# bldcmd_ver1.net
KiCad netlist of a schematic drawn in EAGLE
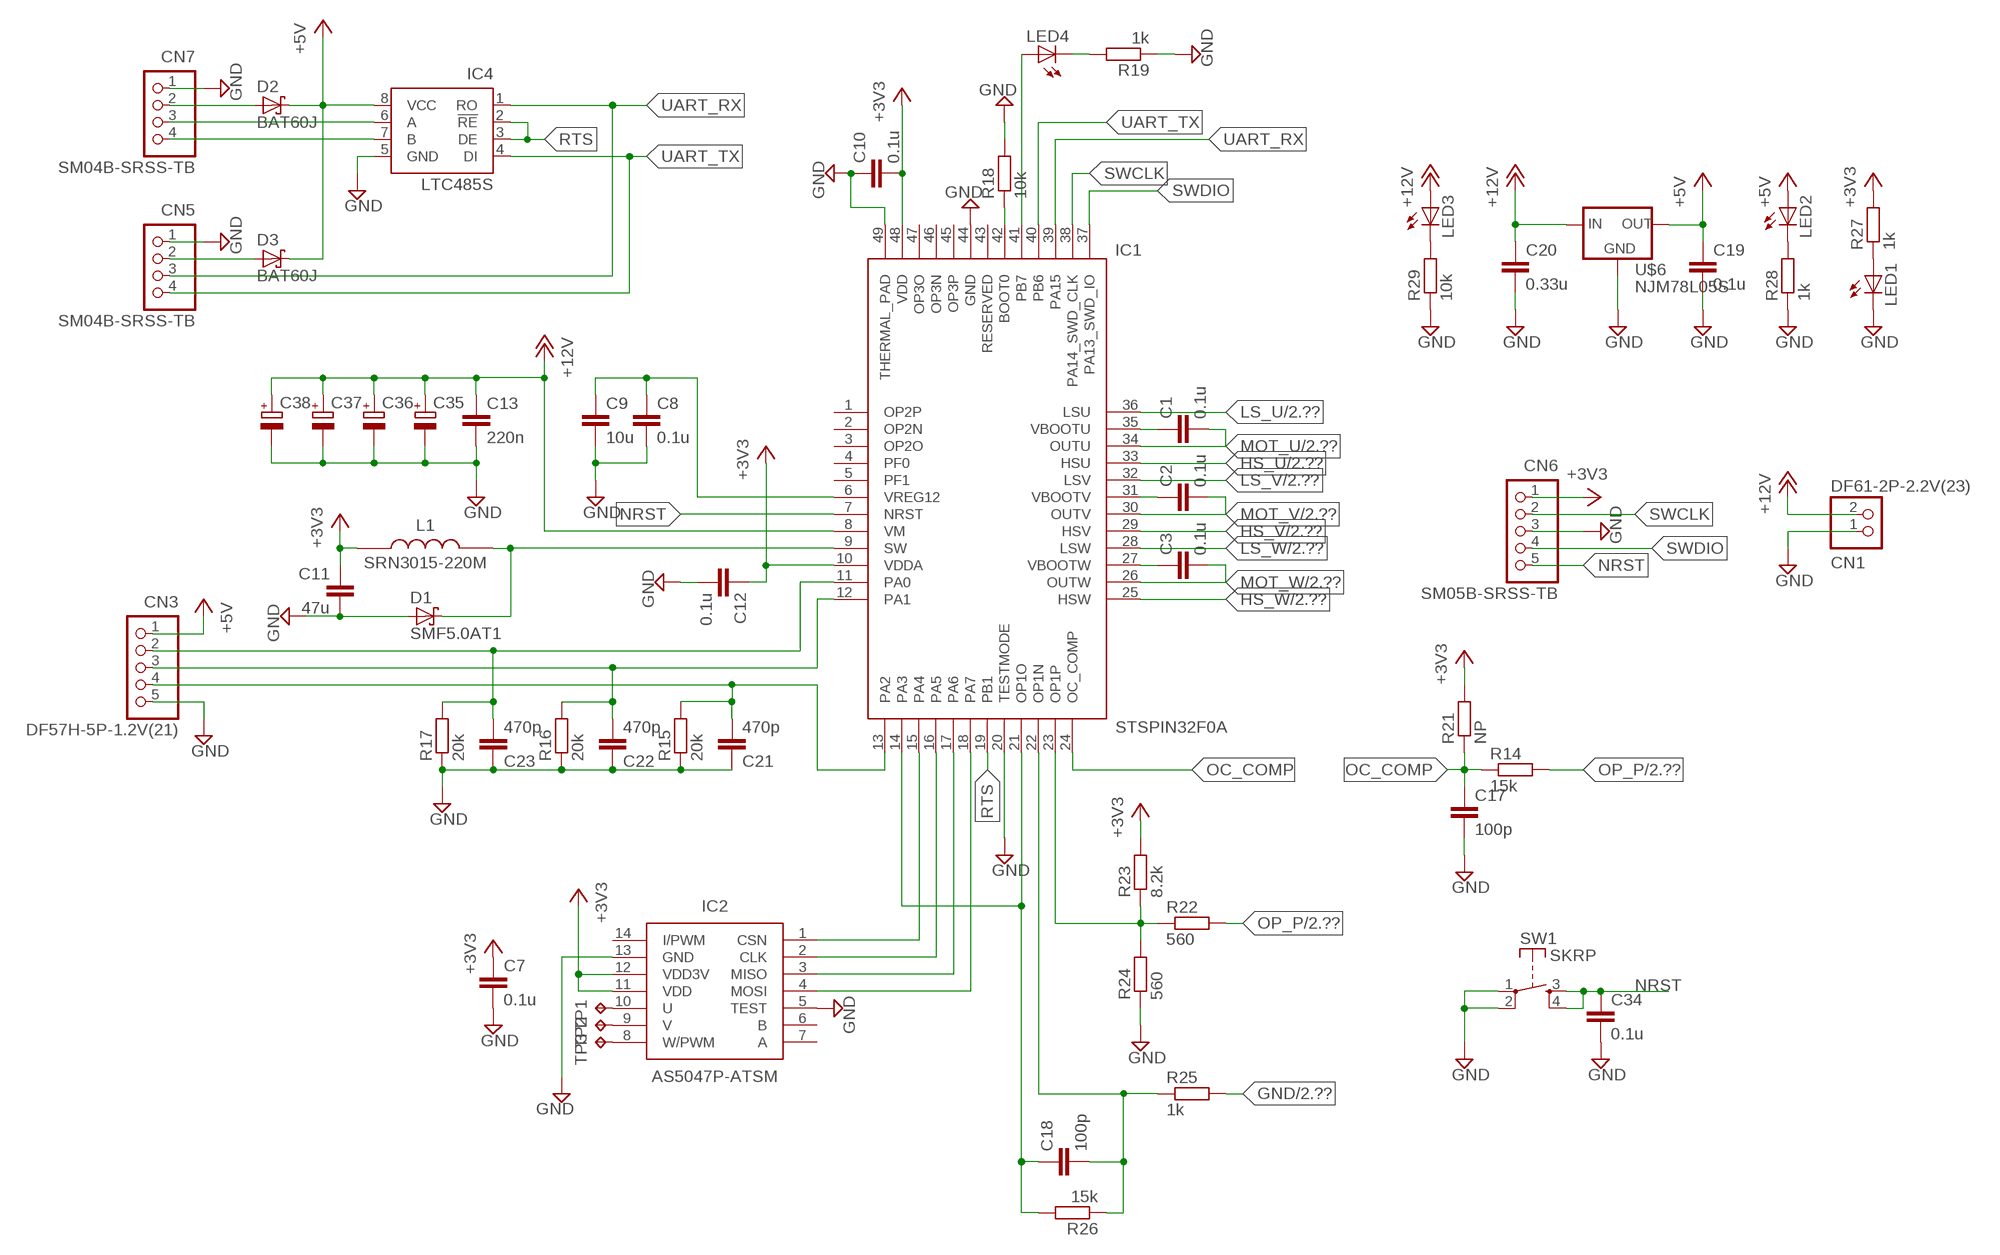
[diagram p0: schematic, sheet 1]
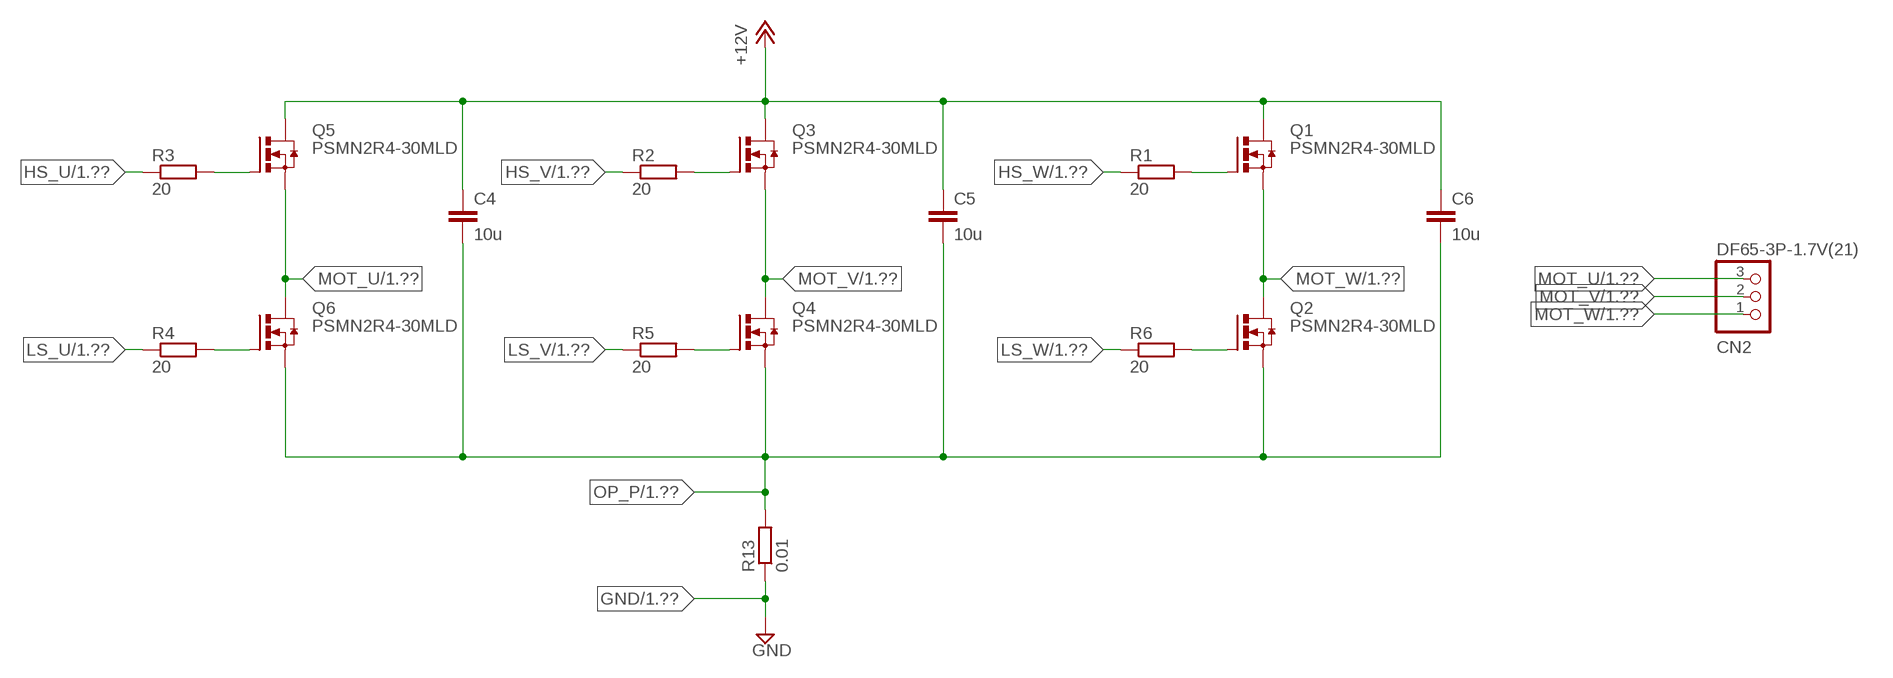
[diagram p1: schematic, sheet 2]

(export (version "E")
  (design (tool "Eeschema 10.0.6"))
  (components
    (comp (ref "C4")
      (value "10u")
      (footprint "eagle-import:C1206")
      (libsource (lib "eagle-import") (part "C-EUC1206"))
    )
    (comp (ref "C5")
      (value "10u")
      (footprint "eagle-import:C1206")
      (libsource (lib "eagle-import") (part "C-EUC1206"))
    )
    (comp (ref "C6")
      (value "10u")
      (footprint "eagle-import:C1206")
      (libsource (lib "eagle-import") (part "C-EUC1206"))
    )
    (comp (ref "CN2")
      (value "DF65-3P-1.7V(21)")
      (footprint "eagle-import:DF65-3P-1.7V")
      (fields (field (name "RS_PART_NUMBER") "8735164"))
      (libsource (lib "eagle-import") (part "DF65-3P-1.7V(21)"))
    )
    (comp (ref "Q1")
      (value "PSMN2R4-30MLD")
      (footprint "eagle-import:LFPAK33")
      (fields (field (name "MF") "Nexperia USA Inc.") (field (name "MPN") "PSMN2R4-30MLD "))
      (libsource (lib "eagle-import") (part "PSMN2R4-30MLD"))
    )
    (comp (ref "Q2")
      (value "PSMN2R4-30MLD")
      (footprint "eagle-import:LFPAK33")
      (fields (field (name "MF") "Nexperia USA Inc.") (field (name "MPN") "PSMN2R4-30MLD "))
      (libsource (lib "eagle-import") (part "PSMN2R4-30MLD"))
    )
    (comp (ref "Q3")
      (value "PSMN2R4-30MLD")
      (footprint "eagle-import:LFPAK33")
      (fields (field (name "MF") "Nexperia USA Inc.") (field (name "MPN") "PSMN2R4-30MLD "))
      (libsource (lib "eagle-import") (part "PSMN2R4-30MLD"))
    )
    (comp (ref "Q4")
      (value "PSMN2R4-30MLD")
      (footprint "eagle-import:LFPAK33")
      (fields (field (name "MF") "Nexperia USA Inc.") (field (name "MPN") "PSMN2R4-30MLD "))
      (libsource (lib "eagle-import") (part "PSMN2R4-30MLD"))
    )
    (comp (ref "Q5")
      (value "PSMN2R4-30MLD")
      (footprint "eagle-import:LFPAK33")
      (fields (field (name "MF") "Nexperia USA Inc.") (field (name "MPN") "PSMN2R4-30MLD "))
      (libsource (lib "eagle-import") (part "PSMN2R4-30MLD"))
    )
    (comp (ref "Q6")
      (value "PSMN2R4-30MLD")
      (footprint "eagle-import:LFPAK33")
      (fields (field (name "MF") "Nexperia USA Inc.") (field (name "MPN") "PSMN2R4-30MLD "))
      (libsource (lib "eagle-import") (part "PSMN2R4-30MLD"))
    )
    (comp (ref "R1")
      (value "20")
      (footprint "eagle-import:R0603")
      (libsource (lib "eagle-import") (part "R-EU_R0603"))
    )
    (comp (ref "R2")
      (value "20")
      (footprint "eagle-import:R0603")
      (libsource (lib "eagle-import") (part "R-EU_R0603"))
    )
    (comp (ref "R3")
      (value "20")
      (footprint "eagle-import:R0603")
      (libsource (lib "eagle-import") (part "R-EU_R0603"))
    )
    (comp (ref "R4")
      (value "20")
      (footprint "eagle-import:R0603")
      (libsource (lib "eagle-import") (part "R-EU_R0603"))
    )
    (comp (ref "R5")
      (value "20")
      (footprint "eagle-import:R0603")
      (libsource (lib "eagle-import") (part "R-EU_R0603"))
    )
    (comp (ref "R6")
      (value "20")
      (footprint "eagle-import:R0603")
      (libsource (lib "eagle-import") (part "R-EU_R0603"))
    )
    (comp (ref "R13")
      (value "0.01")
      (footprint "eagle-import:R3216")
      (libsource (lib "eagle-import") (part "R-EU_R3216"))
    )
    (comp (ref "C1")
      (value "0.1u")
      (footprint "eagle-import:C0402")
      (libsource (lib "eagle-import") (part "C-EUC0402"))
    )
    (comp (ref "C2")
      (value "0.1u")
      (footprint "eagle-import:C0402")
      (libsource (lib "eagle-import") (part "C-EUC0402"))
    )
    (comp (ref "C3")
      (value "0.1u")
      (footprint "eagle-import:C0402")
      (libsource (lib "eagle-import") (part "C-EUC0402"))
    )
    (comp (ref "C7")
      (value "0.1u")
      (footprint "eagle-import:C0603K")
      (libsource (lib "eagle-import") (part "C-EUC0603K"))
    )
    (comp (ref "C8")
      (value "0.1u")
      (footprint "eagle-import:C0603K")
      (libsource (lib "eagle-import") (part "C-EUC0603K"))
    )
    (comp (ref "C9")
      (value "10u")
      (footprint "eagle-import:C0805K")
      (libsource (lib "eagle-import") (part "C-EUC0805K"))
    )
    (comp (ref "C10")
      (value "0.1u")
      (footprint "eagle-import:C0603K")
      (libsource (lib "eagle-import") (part "C-EUC0603K"))
    )
    (comp (ref "C11")
      (value "47u")
      (footprint "eagle-import:C1206K")
      (libsource (lib "eagle-import") (part "C-EUC1206K"))
    )
    (comp (ref "C12")
      (value "0.1u")
      (footprint "eagle-import:C0603K")
      (libsource (lib "eagle-import") (part "C-EUC0603K"))
    )
    (comp (ref "C13")
      (value "220n")
      (footprint "eagle-import:C0805K")
      (libsource (lib "eagle-import") (part "C-EUC0805K"))
    )
    (comp (ref "C17")
      (value "100p")
      (footprint "eagle-import:C0402")
      (libsource (lib "eagle-import") (part "C-EUC0402"))
    )
    (comp (ref "C18")
      (value "100p")
      (footprint "eagle-import:C0402")
      (libsource (lib "eagle-import") (part "C-EUC0402"))
    )
    (comp (ref "C19")
      (value "0.1u")
      (footprint "eagle-import:C0603K")
      (libsource (lib "eagle-import") (part "C-EUC0603K"))
    )
    (comp (ref "C20")
      (value "0.33u")
      (footprint "eagle-import:C0805K")
      (libsource (lib "eagle-import") (part "C-EUC0805K"))
    )
    (comp (ref "C21")
      (value "470p")
      (footprint "eagle-import:C0402")
      (libsource (lib "eagle-import") (part "C-EUC0402"))
    )
    (comp (ref "C22")
      (value "470p")
      (footprint "eagle-import:C0402")
      (libsource (lib "eagle-import") (part "C-EUC0402"))
    )
    (comp (ref "C23")
      (value "470p")
      (footprint "eagle-import:C0402")
      (libsource (lib "eagle-import") (part "C-EUC0402"))
    )
    (comp (ref "C34")
      (value "0.1u")
      (footprint "eagle-import:C0603K")
      (libsource (lib "eagle-import") (part "C-EUC0603K"))
    )
    (comp (ref "C35")
      (value "CPOL-EU153CLV-0605")
      (footprint "eagle-import:153CLV-0605")
      (libsource (lib "eagle-import") (part "CPOL-EU153CLV-0605"))
    )
    (comp (ref "C36")
      (value "CPOL-EU153CLV-0605")
      (footprint "eagle-import:153CLV-0605")
      (libsource (lib "eagle-import") (part "CPOL-EU153CLV-0605"))
    )
    (comp (ref "C37")
      (value "CPOL-EU153CLV-0605")
      (footprint "eagle-import:153CLV-0605")
      (libsource (lib "eagle-import") (part "CPOL-EU153CLV-0605"))
    )
    (comp (ref "C38")
      (value "CPOL-EU153CLV-0605")
      (footprint "eagle-import:153CLV-0605")
      (libsource (lib "eagle-import") (part "CPOL-EU153CLV-0605"))
    )
    (comp (ref "CN1")
      (value "DF61-2P-2.2V(23)")
      (footprint "eagle-import:DF61-2P-2.2V")
      (fields (field (name "RS_PART_NUMBER") "7922837P"))
      (libsource (lib "eagle-import") (part "DF61-2P-2.2V(23)"))
    )
    (comp (ref "CN3")
      (value "DF57H-5P-1.2V(21)")
      (footprint "eagle-import:DF57H-5P-1.2V(21)")
      (libsource (lib "eagle-import") (part "DF57H-5P-1.2V(21)"))
    )
    (comp (ref "CN5")
      (value "SM04B-SRSS-TB")
      (footprint "eagle-import:SM04B-SRSS-TB")
      (libsource (lib "eagle-import") (part "?M04B-SRSS-TBS"))
    )
    (comp (ref "CN6")
      (value "SM05B-SRSS-TB")
      (footprint "eagle-import:SM05B-SRSS-TB")
      (libsource (lib "eagle-import") (part "?M05B-SRSS-TBS"))
    )
    (comp (ref "CN7")
      (value "SM04B-SRSS-TB")
      (footprint "eagle-import:SM04B-SRSS-TB")
      (libsource (lib "eagle-import") (part "?M04B-SRSS-TBS"))
    )
    (comp (ref "D1")
      (value "SMF5.0AT1")
      (footprint "eagle-import:SOD123FL")
      (libsource (lib "eagle-import") (part "SMF5.0AT1"))
    )
    (comp (ref "D2")
      (value "BAT60J")
      (footprint "eagle-import:SOD323_ST")
      (libsource (lib "eagle-import") (part "BAT60J"))
    )
    (comp (ref "D3")
      (value "BAT60J")
      (footprint "eagle-import:SOD323_ST")
      (libsource (lib "eagle-import") (part "BAT60J"))
    )
    (comp (ref "IC1")
      (value "STSPIN32F0A")
      (footprint "eagle-import:VFQFPN48_7X7X1.0-48L")
      (fields (field (name "MANUFACTURER_PART_NUMBER") "STSPIN32F0ATR"))
      (libsource (lib "eagle-import") (part "STSPIN32F0A"))
    )
    (comp (ref "IC2")
      (value "AS5047P-ATSM")
      (footprint "eagle-import:SOP65P640X120-14N")
      (libsource (lib "eagle-import") (part "AS5047P-ATSM"))
    )
    (comp (ref "IC4")
      (value "LTC485S")
      (footprint "eagle-import:SOIC8")
      (libsource (lib "eagle-import") (part "LTC485S"))
    )
    (comp (ref "L1")
      (value "SRN3015-220M")
      (footprint "eagle-import:SRN3015")
      (fields (field (name "RS_PART_NUMBER") "7435087"))
      (libsource (lib "eagle-import") (part "SRN3015-220M"))
    )
    (comp (ref "LED1")
      (value "LEDSML0603")
      (footprint "eagle-import:SML0603")
      (libsource (lib "eagle-import") (part "LEDSML0603"))
    )
    (comp (ref "LED2")
      (value "LEDSML0603")
      (footprint "eagle-import:SML0603")
      (libsource (lib "eagle-import") (part "LEDSML0603"))
    )
    (comp (ref "LED3")
      (value "LEDSML0603")
      (footprint "eagle-import:SML0603")
      (libsource (lib "eagle-import") (part "LEDSML0603"))
    )
    (comp (ref "LED4")
      (value "LEDSML0603")
      (footprint "eagle-import:SML0603")
      (libsource (lib "eagle-import") (part "LEDSML0603"))
    )
    (comp (ref "R14")
      (value "15k")
      (footprint "eagle-import:R0402")
      (libsource (lib "eagle-import") (part "R-EU_R0402"))
    )
    (comp (ref "R15")
      (value "20k")
      (footprint "eagle-import:R0402")
      (libsource (lib "eagle-import") (part "R-EU_R0402"))
    )
    (comp (ref "R16")
      (value "20k")
      (footprint "eagle-import:R0402")
      (libsource (lib "eagle-import") (part "R-EU_R0402"))
    )
    (comp (ref "R17")
      (value "20k")
      (footprint "eagle-import:R0402")
      (libsource (lib "eagle-import") (part "R-EU_R0402"))
    )
    (comp (ref "R18")
      (value "10k")
      (footprint "eagle-import:R0402")
      (libsource (lib "eagle-import") (part "R-EU_R0402"))
    )
    (comp (ref "R19")
      (value "1k")
      (footprint "eagle-import:R0603")
      (libsource (lib "eagle-import") (part "R-EU_R0603"))
    )
    (comp (ref "R21")
      (value "NP")
      (footprint "eagle-import:R0402")
      (libsource (lib "eagle-import") (part "R-EU_R0402"))
    )
    (comp (ref "R22")
      (value "560")
      (footprint "eagle-import:R0402")
      (libsource (lib "eagle-import") (part "R-EU_R0402"))
    )
    (comp (ref "R23")
      (value "8.2k")
      (footprint "eagle-import:R0402")
      (libsource (lib "eagle-import") (part "R-EU_R0402"))
    )
    (comp (ref "R24")
      (value "560")
      (footprint "eagle-import:R0402")
      (libsource (lib "eagle-import") (part "R-EU_R0402"))
    )
    (comp (ref "R25")
      (value "1k")
      (footprint "eagle-import:R0402")
      (libsource (lib "eagle-import") (part "R-EU_R0402"))
    )
    (comp (ref "R26")
      (value "15k")
      (footprint "eagle-import:R0402")
      (libsource (lib "eagle-import") (part "R-EU_R0402"))
    )
    (comp (ref "R27")
      (value "1k")
      (footprint "eagle-import:R0603")
      (libsource (lib "eagle-import") (part "R-EU_R0603"))
    )
    (comp (ref "R28")
      (value "1k")
      (footprint "eagle-import:R0603")
      (libsource (lib "eagle-import") (part "R-EU_R0603"))
    )
    (comp (ref "R29")
      (value "10k")
      (footprint "eagle-import:R0603")
      (libsource (lib "eagle-import") (part "R-EU_R0603"))
    )
    (comp (ref "SW1")
      (value "SKRP")
      (footprint "eagle-import:SKRP")
      (libsource (lib "eagle-import") (part "SKRP"))
    )
    (comp (ref "TP1")
      (value "TPTP08R")
      (footprint "eagle-import:TP08R")
      (libsource (lib "eagle-import") (part "TPTP08R"))
    )
    (comp (ref "TP2")
      (value "TPTP08R")
      (footprint "eagle-import:TP08R")
      (libsource (lib "eagle-import") (part "TPTP08R"))
    )
    (comp (ref "TP3")
      (value "TPTP08R")
      (footprint "eagle-import:TP08R")
      (libsource (lib "eagle-import") (part "TPTP08R"))
    )
    (comp (ref "U$6")
      (value "NJM78L05S")
      (footprint "eagle-import:SOT89R")
      (libsource (lib "eagle-import") (part "NJM78L?S05"))
    )
  )
  (nets
    (net (code "1") (name "+3V3") (class "Default")
      (node (ref "C10") (pin "2") (pinfunction "2_2") (pintype "passive"))
      (node (ref "C11") (pin "1") (pinfunction "1_1") (pintype "passive"))
      (node (ref "C12") (pin "1") (pinfunction "1_1") (pintype "passive"))
      (node (ref "C7") (pin "1") (pinfunction "1_1") (pintype "passive"))
      (node (ref "CN6") (pin "1") (pinfunction "1_1") (pintype "passive"))
      (node (ref "IC1") (pin "10") (pinfunction "VDDA_10") (pintype "passive"))
      (node (ref "IC1") (pin "48") (pinfunction "VDD_48") (pintype "passive"))
      (node (ref "IC2") (pin "11") (pinfunction "VDD_11") (pintype "passive"))
      (node (ref "IC2") (pin "12") (pinfunction "VDD3V_12") (pintype "passive"))
      (node (ref "L1") (pin "1") (pinfunction "1_1") (pintype "bidirectional"))
      (node (ref "R21") (pin "2") (pinfunction "2_2") (pintype "passive"))
      (node (ref "R23") (pin "2") (pinfunction "2_2") (pintype "passive"))
      (node (ref "R27") (pin "2") (pinfunction "2_2") (pintype "passive"))
    )
    (net (code "2") (name "+5V") (class "Default")
      (node (ref "C19") (pin "1") (pinfunction "1_1") (pintype "passive"))
      (node (ref "CN3") (pin "1") (pinfunction "1_1") (pintype "passive"))
      (node (ref "D2") (pin "C") (pinfunction "C_C") (pintype "passive"))
      (node (ref "D3") (pin "C") (pinfunction "C_C") (pintype "passive"))
      (node (ref "IC4") (pin "8") (pinfunction "VCC_8") (pintype "input"))
      (node (ref "LED2") (pin "A") (pinfunction "A_A") (pintype "passive"))
      (node (ref "U$6") (pin "2") (pinfunction "OUT_2") (pintype "passive"))
    )
    (net (code "3") (name "+12V") (class "Default")
      (node (ref "C13") (pin "1") (pinfunction "1_1") (pintype "passive"))
      (node (ref "C20") (pin "1") (pinfunction "1_1") (pintype "passive"))
      (node (ref "C35") (pin "+") (pinfunction "+_+") (pintype "passive"))
      (node (ref "C36") (pin "+") (pinfunction "+_+") (pintype "passive"))
      (node (ref "C37") (pin "+") (pinfunction "+_+") (pintype "passive"))
      (node (ref "C38") (pin "+") (pinfunction "+_+") (pintype "passive"))
      (node (ref "C4") (pin "1") (pinfunction "1_1") (pintype "passive"))
      (node (ref "C5") (pin "1") (pinfunction "1_1") (pintype "passive"))
      (node (ref "C6") (pin "1") (pinfunction "1_1") (pintype "passive"))
      (node (ref "CN1") (pin "2") (pinfunction "2_2") (pintype "passive"))
      (node (ref "IC1") (pin "8") (pinfunction "VM_8") (pintype "passive"))
      (node (ref "LED3") (pin "A") (pinfunction "A_A") (pintype "passive"))
      (node (ref "Q1") (pin "MB") (pinfunction "D_MB") (pintype "passive"))
      (node (ref "Q3") (pin "MB") (pinfunction "D_MB") (pintype "passive"))
      (node (ref "Q5") (pin "MB") (pinfunction "D_MB") (pintype "passive"))
      (node (ref "U$6") (pin "1") (pinfunction "IN_1") (pintype "input"))
    )
    (net (code "4") (name "GND") (class "Default")
      (node (ref "C10") (pin "1") (pinfunction "1_1") (pintype "passive"))
      (node (ref "C11") (pin "2") (pinfunction "2_2") (pintype "passive"))
      (node (ref "C12") (pin "2") (pinfunction "2_2") (pintype "passive"))
      (node (ref "C13") (pin "2") (pinfunction "2_2") (pintype "passive"))
      (node (ref "C17") (pin "2") (pinfunction "2_2") (pintype "passive"))
      (node (ref "C19") (pin "2") (pinfunction "2_2") (pintype "passive"))
      (node (ref "C20") (pin "2") (pinfunction "2_2") (pintype "passive"))
      (node (ref "C21") (pin "1") (pinfunction "1_1") (pintype "passive"))
      (node (ref "C22") (pin "1") (pinfunction "1_1") (pintype "passive"))
      (node (ref "C23") (pin "1") (pinfunction "1_1") (pintype "passive"))
      (node (ref "C34") (pin "2") (pinfunction "2_2") (pintype "passive"))
      (node (ref "C35") (pin "-") (pinfunction "-_-") (pintype "passive"))
      (node (ref "C36") (pin "-") (pinfunction "-_-") (pintype "passive"))
      (node (ref "C37") (pin "-") (pinfunction "-_-") (pintype "passive"))
      (node (ref "C38") (pin "-") (pinfunction "-_-") (pintype "passive"))
      (node (ref "C7") (pin "2") (pinfunction "2_2") (pintype "passive"))
      (node (ref "C8") (pin "2") (pinfunction "2_2") (pintype "passive"))
      (node (ref "C9") (pin "2") (pinfunction "2_2") (pintype "passive"))
      (node (ref "CN1") (pin "1") (pinfunction "1_1") (pintype "passive"))
      (node (ref "CN3") (pin "5") (pinfunction "5_5") (pintype "passive"))
      (node (ref "CN5") (pin "1") (pinfunction "1_1") (pintype "passive"))
      (node (ref "CN6") (pin "3") (pinfunction "3_3") (pintype "passive"))
      (node (ref "CN7") (pin "1") (pinfunction "1_1") (pintype "passive"))
      (node (ref "D1") (pin "A") (pinfunction "A_A") (pintype "passive"))
      (node (ref "IC1") (pin "20") (pinfunction "TESTMODE_20") (pintype "passive"))
      (node (ref "IC1") (pin "44") (pinfunction "GND_44") (pintype "passive"))
      (node (ref "IC1") (pin "49") (pinfunction "THERMAL_PAD_49") (pintype "passive"))
      (node (ref "IC2") (pin "13") (pinfunction "GND_13") (pintype "passive"))
      (node (ref "IC2") (pin "5") (pinfunction "TEST_5") (pintype "passive"))
      (node (ref "IC4") (pin "5") (pinfunction "GND_5") (pintype "input"))
      (node (ref "LED1") (pin "C") (pinfunction "C_C") (pintype "passive"))
      (node (ref "R13") (pin "1") (pinfunction "1_1") (pintype "passive"))
      (node (ref "R15") (pin "1") (pinfunction "1_1") (pintype "passive"))
      (node (ref "R16") (pin "1") (pinfunction "1_1") (pintype "passive"))
      (node (ref "R17") (pin "1") (pinfunction "1_1") (pintype "passive"))
      (node (ref "R18") (pin "2") (pinfunction "2_2") (pintype "passive"))
      (node (ref "R19") (pin "1") (pinfunction "1_1") (pintype "passive"))
      (node (ref "R24") (pin "1") (pinfunction "1_1") (pintype "passive"))
      (node (ref "R25") (pin "2") (pinfunction "2_2") (pintype "passive"))
      (node (ref "R28") (pin "1") (pinfunction "1_1") (pintype "passive"))
      (node (ref "R29") (pin "1") (pinfunction "1_1") (pintype "passive"))
      (node (ref "SW1") (pin "1") (pinfunction "1_1") (pintype "passive"))
      (node (ref "SW1") (pin "2") (pinfunction "2_2") (pintype "passive"))
      (node (ref "U$6") (pin "3") (pinfunction "GND_3") (pintype "input"))
      (node (ref "U$6") (pin "4") (pinfunction "GND_4") (pintype "input"))
    )
    (net (code "5") (name "HS_U") (class "Default")
      (node (ref "IC1") (pin "33") (pinfunction "HSU_33") (pintype "passive"))
      (node (ref "R3") (pin "1") (pinfunction "1_1") (pintype "passive"))
    )
    (net (code "6") (name "HS_V") (class "Default")
      (node (ref "IC1") (pin "29") (pinfunction "HSV_29") (pintype "passive"))
      (node (ref "R2") (pin "1") (pinfunction "1_1") (pintype "passive"))
    )
    (net (code "7") (name "HS_W") (class "Default")
      (node (ref "IC1") (pin "25") (pinfunction "HSW_25") (pintype "passive"))
      (node (ref "R1") (pin "1") (pinfunction "1_1") (pintype "passive"))
    )
    (net (code "8") (name "LS_U") (class "Default")
      (node (ref "IC1") (pin "36") (pinfunction "LSU_36") (pintype "passive"))
      (node (ref "R4") (pin "1") (pinfunction "1_1") (pintype "passive"))
    )
    (net (code "9") (name "LS_V") (class "Default")
      (node (ref "IC1") (pin "32") (pinfunction "LSV_32") (pintype "passive"))
      (node (ref "R5") (pin "1") (pinfunction "1_1") (pintype "passive"))
    )
    (net (code "10") (name "LS_W") (class "Default")
      (node (ref "IC1") (pin "28") (pinfunction "LSW_28") (pintype "passive"))
      (node (ref "R6") (pin "1") (pinfunction "1_1") (pintype "passive"))
    )
    (net (code "11") (name "MOT_U") (class "Default")
      (node (ref "C1") (pin "2") (pinfunction "2_2") (pintype "passive"))
      (node (ref "CN2") (pin "3") (pinfunction "3_3") (pintype "passive"))
      (node (ref "IC1") (pin "34") (pinfunction "OUTU_34") (pintype "passive"))
      (node (ref "Q5") (pin "1") (pinfunction "S_1") (pintype "passive"))
      (node (ref "Q5") (pin "2") (pinfunction "S_2") (pintype "passive"))
      (node (ref "Q5") (pin "3") (pinfunction "S_3") (pintype "passive"))
      (node (ref "Q6") (pin "MB") (pinfunction "D_MB") (pintype "passive"))
    )
    (net (code "12") (name "MOT_V") (class "Default")
      (node (ref "C2") (pin "2") (pinfunction "2_2") (pintype "passive"))
      (node (ref "CN2") (pin "2") (pinfunction "2_2") (pintype "passive"))
      (node (ref "IC1") (pin "30") (pinfunction "OUTV_30") (pintype "passive"))
      (node (ref "Q3") (pin "1") (pinfunction "S_1") (pintype "passive"))
      (node (ref "Q3") (pin "2") (pinfunction "S_2") (pintype "passive"))
      (node (ref "Q3") (pin "3") (pinfunction "S_3") (pintype "passive"))
      (node (ref "Q4") (pin "MB") (pinfunction "D_MB") (pintype "passive"))
    )
    (net (code "13") (name "MOT_W") (class "Default")
      (node (ref "C3") (pin "2") (pinfunction "2_2") (pintype "passive"))
      (node (ref "CN2") (pin "1") (pinfunction "1_1") (pintype "passive"))
      (node (ref "IC1") (pin "26") (pinfunction "OUTW_26") (pintype "passive"))
      (node (ref "Q1") (pin "1") (pinfunction "S_1") (pintype "passive"))
      (node (ref "Q1") (pin "2") (pinfunction "S_2") (pintype "passive"))
      (node (ref "Q1") (pin "3") (pinfunction "S_3") (pintype "passive"))
      (node (ref "Q2") (pin "MB") (pinfunction "D_MB") (pintype "passive"))
    )
    (net (code "14") (name "NRST") (class "Default")
      (node (ref "C34") (pin "1") (pinfunction "1_1") (pintype "passive"))
      (node (ref "CN6") (pin "5") (pinfunction "5_5") (pintype "passive"))
      (node (ref "IC1") (pin "7") (pinfunction "NRST_7") (pintype "passive"))
      (node (ref "SW1") (pin "3") (pinfunction "3_3") (pintype "passive"))
      (node (ref "SW1") (pin "4") (pinfunction "4_4") (pintype "passive"))
    )
    (net (code "15") (name "Net-(CN5-Pad2)") (class "Default")
      (node (ref "CN5") (pin "2") (pinfunction "2_2") (pintype "passive"))
      (node (ref "D3") (pin "A") (pinfunction "A_A") (pintype "passive"))
    )
    (net (code "16") (name "Net-(CN7-Pad2)") (class "Default")
      (node (ref "CN7") (pin "2") (pinfunction "2_2") (pintype "passive"))
      (node (ref "D2") (pin "A") (pinfunction "A_A") (pintype "passive"))
    )
    (net (code "17") (name "Net-(IC1-BOOT0)") (class "Default")
      (node (ref "IC1") (pin "42") (pinfunction "BOOT0_42") (pintype "passive"))
      (node (ref "R18") (pin "1") (pinfunction "1_1") (pintype "passive"))
    )
    (net (code "18") (name "Net-(IC1-OP1N)") (class "Default")
      (node (ref "C18") (pin "2") (pinfunction "2_2") (pintype "passive"))
      (node (ref "IC1") (pin "22") (pinfunction "OP1N_22") (pintype "passive"))
      (node (ref "R25") (pin "1") (pinfunction "1_1") (pintype "passive"))
      (node (ref "R26") (pin "1") (pinfunction "1_1") (pintype "passive"))
    )
    (net (code "19") (name "Net-(IC1-OP1O)") (class "Default")
      (node (ref "C18") (pin "1") (pinfunction "1_1") (pintype "passive"))
      (node (ref "IC1") (pin "14") (pinfunction "PA3_14") (pintype "passive"))
      (node (ref "IC1") (pin "21") (pinfunction "OP1O_21") (pintype "passive"))
      (node (ref "R26") (pin "2") (pinfunction "2_2") (pintype "passive"))
    )
    (net (code "20") (name "Net-(IC1-OP1P)") (class "Default")
      (node (ref "IC1") (pin "23") (pinfunction "OP1P_23") (pintype "passive"))
      (node (ref "R22") (pin "1") (pinfunction "1_1") (pintype "passive"))
      (node (ref "R23") (pin "1") (pinfunction "1_1") (pintype "passive"))
      (node (ref "R24") (pin "2") (pinfunction "2_2") (pintype "passive"))
    )
    (net (code "21") (name "Net-(IC1-PA0)") (class "Default")
      (node (ref "C23") (pin "2") (pinfunction "2_2") (pintype "passive"))
      (node (ref "CN3") (pin "2") (pinfunction "2_2") (pintype "passive"))
      (node (ref "IC1") (pin "11") (pinfunction "PA0_11") (pintype "passive"))
      (node (ref "R17") (pin "2") (pinfunction "2_2") (pintype "passive"))
    )
    (net (code "22") (name "Net-(IC1-PA1)") (class "Default")
      (node (ref "C22") (pin "2") (pinfunction "2_2") (pintype "passive"))
      (node (ref "CN3") (pin "3") (pinfunction "3_3") (pintype "passive"))
      (node (ref "IC1") (pin "12") (pinfunction "PA1_12") (pintype "passive"))
      (node (ref "R16") (pin "2") (pinfunction "2_2") (pintype "passive"))
    )
    (net (code "23") (name "Net-(IC1-PA2)") (class "Default")
      (node (ref "C21") (pin "2") (pinfunction "2_2") (pintype "passive"))
      (node (ref "CN3") (pin "4") (pinfunction "4_4") (pintype "passive"))
      (node (ref "IC1") (pin "13") (pinfunction "PA2_13") (pintype "passive"))
      (node (ref "R15") (pin "2") (pinfunction "2_2") (pintype "passive"))
    )
    (net (code "24") (name "Net-(IC1-PA4)") (class "Default")
      (node (ref "IC1") (pin "15") (pinfunction "PA4_15") (pintype "passive"))
      (node (ref "IC2") (pin "1") (pinfunction "CSN_1") (pintype "passive"))
    )
    (net (code "25") (name "Net-(IC1-PA5)") (class "Default")
      (node (ref "IC1") (pin "16") (pinfunction "PA5_16") (pintype "passive"))
      (node (ref "IC2") (pin "2") (pinfunction "CLK_2") (pintype "passive"))
    )
    (net (code "26") (name "Net-(IC1-PA6)") (class "Default")
      (node (ref "IC1") (pin "17") (pinfunction "PA6_17") (pintype "passive"))
      (node (ref "IC2") (pin "3") (pinfunction "MISO_3") (pintype "passive"))
    )
    (net (code "27") (name "Net-(IC1-PA7)") (class "Default")
      (node (ref "IC1") (pin "18") (pinfunction "PA7_18") (pintype "passive"))
      (node (ref "IC2") (pin "4") (pinfunction "MOSI_4") (pintype "passive"))
    )
    (net (code "28") (name "Net-(IC1-PB7)") (class "Default")
      (node (ref "IC1") (pin "41") (pinfunction "PB7_41") (pintype "passive"))
      (node (ref "LED4") (pin "A") (pinfunction "A_A") (pintype "passive"))
    )
    (net (code "29") (name "Net-(IC1-SW)") (class "Default")
      (node (ref "D1") (pin "C") (pinfunction "C_C") (pintype "passive"))
      (node (ref "IC1") (pin "9") (pinfunction "SW_9") (pintype "passive"))
      (node (ref "L1") (pin "2") (pinfunction "2_2") (pintype "bidirectional"))
    )
    (net (code "30") (name "Net-(IC1-VBOOTU)") (class "Default")
      (node (ref "C1") (pin "1") (pinfunction "1_1") (pintype "passive"))
      (node (ref "IC1") (pin "35") (pinfunction "VBOOTU_35") (pintype "passive"))
    )
    (net (code "31") (name "Net-(IC1-VBOOTV)") (class "Default")
      (node (ref "C2") (pin "1") (pinfunction "1_1") (pintype "passive"))
      (node (ref "IC1") (pin "31") (pinfunction "VBOOTV_31") (pintype "passive"))
    )
    (net (code "32") (name "Net-(IC1-VBOOTW)") (class "Default")
      (node (ref "C3") (pin "1") (pinfunction "1_1") (pintype "passive"))
      (node (ref "IC1") (pin "27") (pinfunction "VBOOTW_27") (pintype "passive"))
    )
    (net (code "33") (name "Net-(IC1-VREG12)") (class "Default")
      (node (ref "C8") (pin "1") (pinfunction "1_1") (pintype "passive"))
      (node (ref "C9") (pin "1") (pinfunction "1_1") (pintype "passive"))
      (node (ref "IC1") (pin "6") (pinfunction "VREG12_6") (pintype "passive"))
    )
    (net (code "34") (name "Net-(IC2-U)") (class "Default")
      (node (ref "IC2") (pin "10") (pinfunction "U_10") (pintype "passive"))
      (node (ref "TP1") (pin "TP") (pinfunction "TP_TP") (pintype "input"))
    )
    (net (code "35") (name "Net-(IC2-V)") (class "Default")
      (node (ref "IC2") (pin "9") (pinfunction "V_9") (pintype "passive"))
      (node (ref "TP2") (pin "TP") (pinfunction "TP_TP") (pintype "input"))
    )
    (net (code "36") (name "Net-(IC2-W{slash}PWM)") (class "Default")
      (node (ref "IC2") (pin "8") (pinfunction "W/PWM_8") (pintype "passive"))
      (node (ref "TP3") (pin "TP") (pinfunction "TP_TP") (pintype "input"))
    )
    (net (code "37") (name "Net-(IC4-A)") (class "Default")
      (node (ref "CN7") (pin "3") (pinfunction "3_3") (pintype "passive"))
      (node (ref "IC4") (pin "6") (pinfunction "A_6") (pintype "bidirectional"))
    )
    (net (code "38") (name "Net-(IC4-B)") (class "Default")
      (node (ref "CN7") (pin "4") (pinfunction "4_4") (pintype "passive"))
      (node (ref "IC4") (pin "7") (pinfunction "B_7") (pintype "bidirectional"))
    )
    (net (code "39") (name "Net-(LED1-PadA)") (class "Default")
      (node (ref "LED1") (pin "A") (pinfunction "A_A") (pintype "passive"))
      (node (ref "R27") (pin "1") (pinfunction "1_1") (pintype "passive"))
    )
    (net (code "40") (name "Net-(LED2-PadC)") (class "Default")
      (node (ref "LED2") (pin "C") (pinfunction "C_C") (pintype "passive"))
      (node (ref "R28") (pin "2") (pinfunction "2_2") (pintype "passive"))
    )
    (net (code "41") (name "Net-(LED3-PadC)") (class "Default")
      (node (ref "LED3") (pin "C") (pinfunction "C_C") (pintype "passive"))
      (node (ref "R29") (pin "2") (pinfunction "2_2") (pintype "passive"))
    )
    (net (code "42") (name "Net-(LED4-PadC)") (class "Default")
      (node (ref "LED4") (pin "C") (pinfunction "C_C") (pintype "passive"))
      (node (ref "R19") (pin "2") (pinfunction "2_2") (pintype "passive"))
    )
    (net (code "43") (name "Net-(Q1-G)") (class "Default")
      (node (ref "Q1") (pin "4") (pinfunction "G_4") (pintype "passive"))
      (node (ref "R1") (pin "2") (pinfunction "2_2") (pintype "passive"))
    )
    (net (code "44") (name "Net-(Q2-G)") (class "Default")
      (node (ref "Q2") (pin "4") (pinfunction "G_4") (pintype "passive"))
      (node (ref "R6") (pin "2") (pinfunction "2_2") (pintype "passive"))
    )
    (net (code "45") (name "Net-(Q3-G)") (class "Default")
      (node (ref "Q3") (pin "4") (pinfunction "G_4") (pintype "passive"))
      (node (ref "R2") (pin "2") (pinfunction "2_2") (pintype "passive"))
    )
    (net (code "46") (name "Net-(Q4-G)") (class "Default")
      (node (ref "Q4") (pin "4") (pinfunction "G_4") (pintype "passive"))
      (node (ref "R5") (pin "2") (pinfunction "2_2") (pintype "passive"))
    )
    (net (code "47") (name "Net-(Q5-G)") (class "Default")
      (node (ref "Q5") (pin "4") (pinfunction "G_4") (pintype "passive"))
      (node (ref "R3") (pin "2") (pinfunction "2_2") (pintype "passive"))
    )
    (net (code "48") (name "Net-(Q6-G)") (class "Default")
      (node (ref "Q6") (pin "4") (pinfunction "G_4") (pintype "passive"))
      (node (ref "R4") (pin "2") (pinfunction "2_2") (pintype "passive"))
    )
    (net (code "49") (name "OC_COMP") (class "Default")
      (node (ref "C17") (pin "1") (pinfunction "1_1") (pintype "passive"))
      (node (ref "IC1") (pin "24") (pinfunction "OC_COMP_24") (pintype "passive"))
      (node (ref "R14") (pin "1") (pinfunction "1_1") (pintype "passive"))
      (node (ref "R21") (pin "1") (pinfunction "1_1") (pintype "passive"))
    )
    (net (code "50") (name "OP_P") (class "Default")
      (node (ref "C4") (pin "2") (pinfunction "2_2") (pintype "passive"))
      (node (ref "C5") (pin "2") (pinfunction "2_2") (pintype "passive"))
      (node (ref "C6") (pin "2") (pinfunction "2_2") (pintype "passive"))
      (node (ref "Q2") (pin "1") (pinfunction "S_1") (pintype "passive"))
      (node (ref "Q2") (pin "2") (pinfunction "S_2") (pintype "passive"))
      (node (ref "Q2") (pin "3") (pinfunction "S_3") (pintype "passive"))
      (node (ref "Q4") (pin "1") (pinfunction "S_1") (pintype "passive"))
      (node (ref "Q4") (pin "2") (pinfunction "S_2") (pintype "passive"))
      (node (ref "Q4") (pin "3") (pinfunction "S_3") (pintype "passive"))
      (node (ref "Q6") (pin "1") (pinfunction "S_1") (pintype "passive"))
      (node (ref "Q6") (pin "2") (pinfunction "S_2") (pintype "passive"))
      (node (ref "Q6") (pin "3") (pinfunction "S_3") (pintype "passive"))
      (node (ref "R13") (pin "2") (pinfunction "2_2") (pintype "passive"))
      (node (ref "R14") (pin "2") (pinfunction "2_2") (pintype "passive"))
      (node (ref "R22") (pin "2") (pinfunction "2_2") (pintype "passive"))
    )
    (net (code "51") (name "RTS") (class "Default")
      (node (ref "IC1") (pin "19") (pinfunction "PB1_19") (pintype "passive"))
      (node (ref "IC4") (pin "2") (pinfunction "~{RE}_2") (pintype "input"))
      (node (ref "IC4") (pin "3") (pinfunction "DE_3") (pintype "input"))
    )
    (net (code "52") (name "SWCLK") (class "Default")
      (node (ref "CN6") (pin "2") (pinfunction "2_2") (pintype "passive"))
      (node (ref "IC1") (pin "38") (pinfunction "PA14_SWD_CLK_38") (pintype "passive"))
    )
    (net (code "53") (name "SWDIO") (class "Default")
      (node (ref "CN6") (pin "4") (pinfunction "4_4") (pintype "passive"))
      (node (ref "IC1") (pin "37") (pinfunction "PA13_SWD_IO_37") (pintype "passive"))
    )
    (net (code "54") (name "UART_RX") (class "Default")
      (node (ref "CN5") (pin "3") (pinfunction "3_3") (pintype "passive"))
      (node (ref "IC1") (pin "39") (pinfunction "PA15_39") (pintype "passive"))
      (node (ref "IC4") (pin "1") (pinfunction "RO_1") (pintype "output"))
    )
    (net (code "55") (name "UART_TX") (class "Default")
      (node (ref "CN5") (pin "4") (pinfunction "4_4") (pintype "passive"))
      (node (ref "IC1") (pin "40") (pinfunction "PB6_40") (pintype "passive"))
      (node (ref "IC4") (pin "4") (pinfunction "DI_4") (pintype "input"))
    )
    (net (code "56") (name "unconnected-(IC1-OP2N-Pad2)") (class "Default")
      (node (ref "IC1") (pin "2") (pinfunction "OP2N_2") (pintype "passive"))
    )
    (net (code "57") (name "unconnected-(IC1-OP2O-Pad3)") (class "Default")
      (node (ref "IC1") (pin "3") (pinfunction "OP2O_3") (pintype "passive"))
    )
    (net (code "58") (name "unconnected-(IC1-OP2P-Pad1)") (class "Default")
      (node (ref "IC1") (pin "1") (pinfunction "OP2P_1") (pintype "passive"))
    )
    (net (code "59") (name "unconnected-(IC1-OP3N-Pad46)") (class "Default")
      (node (ref "IC1") (pin "46") (pinfunction "OP3N_46") (pintype "passive"))
    )
    (net (code "60") (name "unconnected-(IC1-OP3O-Pad47)") (class "Default")
      (node (ref "IC1") (pin "47") (pinfunction "OP3O_47") (pintype "passive"))
    )
    (net (code "61") (name "unconnected-(IC1-OP3P-Pad45)") (class "Default")
      (node (ref "IC1") (pin "45") (pinfunction "OP3P_45") (pintype "passive"))
    )
    (net (code "62") (name "unconnected-(IC1-PF0-Pad4)") (class "Default")
      (node (ref "IC1") (pin "4") (pinfunction "PF0_4") (pintype "passive"))
    )
    (net (code "63") (name "unconnected-(IC1-PF1-Pad5)") (class "Default")
      (node (ref "IC1") (pin "5") (pinfunction "PF1_5") (pintype "passive"))
    )
    (net (code "64") (name "unconnected-(IC1-RESERVED-Pad43)") (class "Default")
      (node (ref "IC1") (pin "43") (pinfunction "RESERVED_43") (pintype "passive"))
    )
    (net (code "65") (name "unconnected-(IC2-A-Pad7)") (class "Default")
      (node (ref "IC2") (pin "7") (pinfunction "A_7") (pintype "passive"))
    )
    (net (code "66") (name "unconnected-(IC2-B-Pad6)") (class "Default")
      (node (ref "IC2") (pin "6") (pinfunction "B_6") (pintype "passive"))
    )
    (net (code "67") (name "unconnected-(IC2-I{slash}PWM-Pad14)") (class "Default")
      (node (ref "IC2") (pin "14") (pinfunction "I/PWM_14") (pintype "passive"))
    )
  )
)
